# Arduboy_V2.net
KiCad netlist of a schematic drawn in Altium Designer
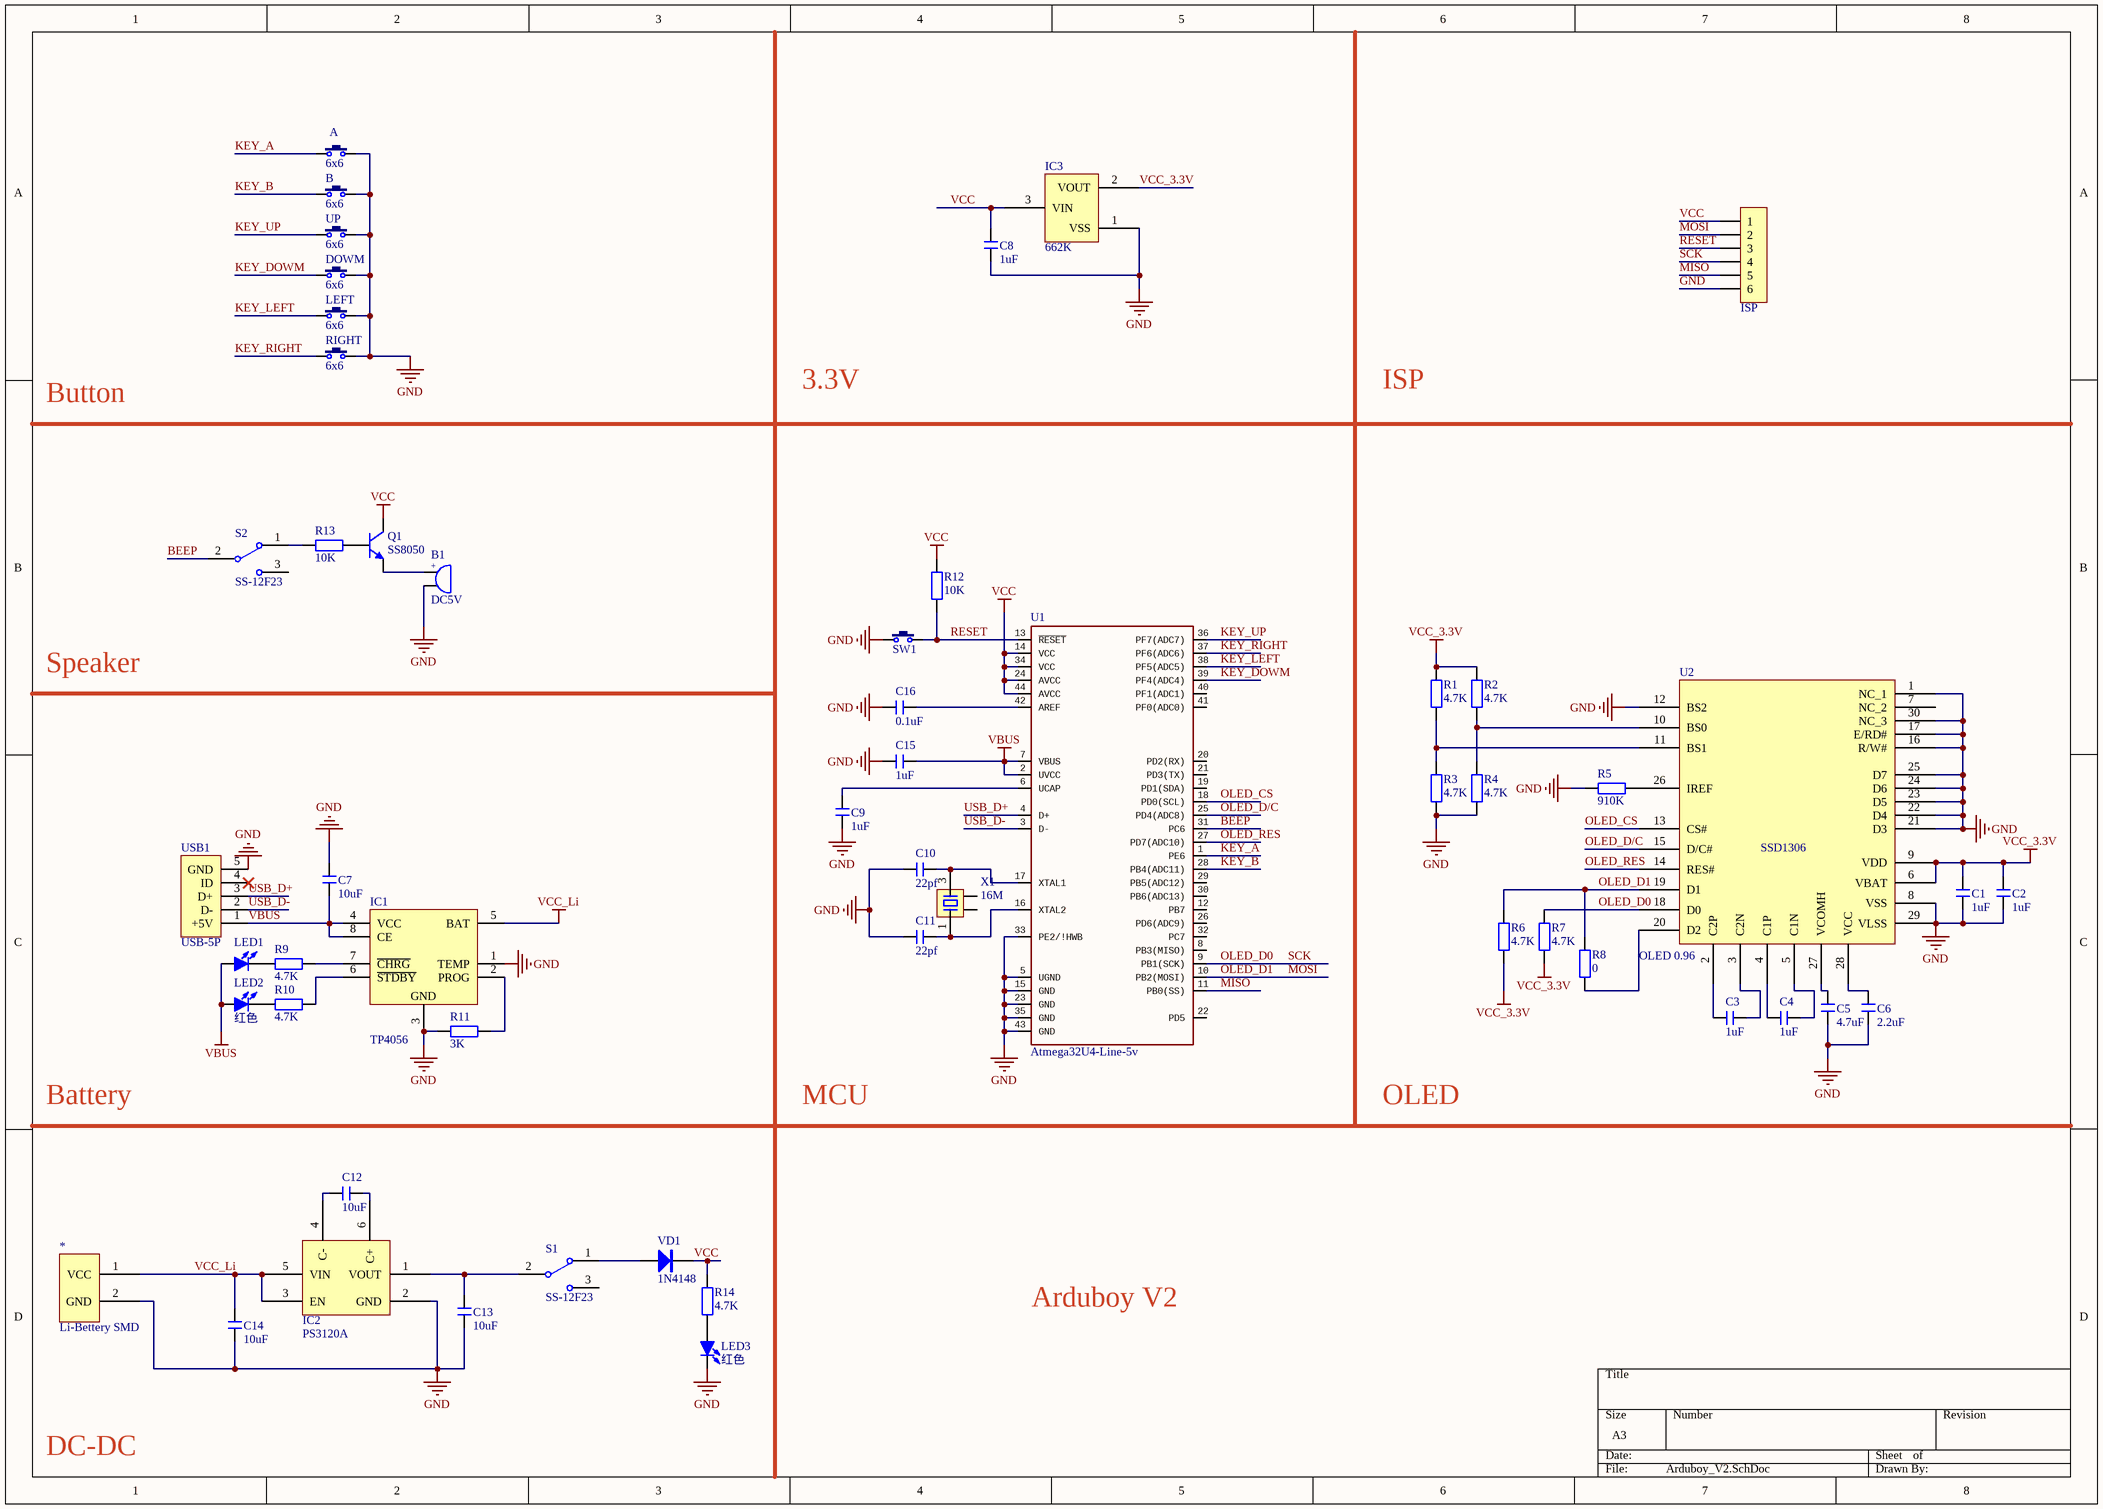
[diagram p0: Arduboy_V2.SchDoc]

(export (version "E")
  (design (tool "Eeschema 10.0.6"))
  (components
    (comp (ref "*")
      (value "Li-Bettery SMD")
      (footprint "Li-Bettery SMD")
      (libsource (lib "未分类器件") (part "Li-Bettery SMD"))
    )
    (comp (ref "A")
      (value "6x6")
      (footprint "SW SMD-2")
      (description "Arduboy 用")
      (libsource (lib "按键-开关") (part "SW SMD-2"))
    )
    (comp (ref "B")
      (value "6x6")
      (footprint "SW SMD-2")
      (description "Arduboy 用")
      (libsource (lib "按键-开关") (part "SW SMD-2"))
    )
    (comp (ref "B1")
      (value "DC5V")
      (footprint "BEEP-SMD 5x5x2")
      (description "蜂鸣器")
      (fields (field (name "版权归属") "黎明电子style"))
      (libsource (lib "未分类器件") (part "BEEP"))
    )
    (comp (ref "C1")
      (value "1uF")
      (footprint "C 0805")
      (description "无极性贴片电容")
      (fields (field (name "版权归属") "黎明电子style"))
      (libsource (lib "电阻-电容-电感") (part "C"))
    )
    (comp (ref "C2")
      (value "1uF")
      (footprint "C 0805")
      (description "无极性贴片电容")
      (fields (field (name "版权归属") "黎明电子style"))
      (libsource (lib "电阻-电容-电感") (part "C"))
    )
    (comp (ref "C3")
      (value "1uF")
      (footprint "C 0805")
      (description "无极性贴片电容")
      (fields (field (name "版权归属") "黎明电子style"))
      (libsource (lib "电阻-电容-电感") (part "C"))
    )
    (comp (ref "C4")
      (value "1uF")
      (footprint "C 0805")
      (description "无极性贴片电容")
      (fields (field (name "版权归属") "黎明电子style"))
      (libsource (lib "电阻-电容-电感") (part "C"))
    )
    (comp (ref "C5")
      (value "4.7uF")
      (footprint "C 0805")
      (description "无极性贴片电容")
      (fields (field (name "版权归属") "黎明电子style"))
      (libsource (lib "电阻-电容-电感") (part "C"))
    )
    (comp (ref "C6")
      (value "2.2uF")
      (footprint "C 0805")
      (description "无极性贴片电容")
      (fields (field (name "版权归属") "黎明电子style"))
      (libsource (lib "电阻-电容-电感") (part "C"))
    )
    (comp (ref "C7")
      (value "10uF")
      (footprint "C 0805")
      (description "无极性贴片电容")
      (fields (field (name "版权归属") "黎明电子style"))
      (libsource (lib "电阻-电容-电感") (part "C"))
    )
    (comp (ref "C8")
      (value "1uF")
      (footprint "C 0805")
      (description "无极性贴片电容")
      (fields (field (name "版权归属") "黎明电子style"))
      (libsource (lib "电阻-电容-电感") (part "C"))
    )
    (comp (ref "C9")
      (value "1uF")
      (footprint "C 0805")
      (description "无极性贴片电容")
      (fields (field (name "版权归属") "黎明电子style"))
      (libsource (lib "电阻-电容-电感") (part "C"))
    )
    (comp (ref "C10")
      (value "22pf")
      (footprint "C 0805")
      (description "无极性贴片电容")
      (fields (field (name "版权归属") "黎明电子style"))
      (libsource (lib "电阻-电容-电感") (part "C"))
    )
    (comp (ref "C11")
      (value "22pf")
      (footprint "C 0805")
      (description "无极性贴片电容")
      (fields (field (name "版权归属") "黎明电子style"))
      (libsource (lib "电阻-电容-电感") (part "C"))
    )
    (comp (ref "C12")
      (value "10uF")
      (footprint "C 0805")
      (description "无极性贴片电容")
      (fields (field (name "版权归属") "黎明电子style"))
      (libsource (lib "电阻-电容-电感") (part "C"))
    )
    (comp (ref "C13")
      (value "10uF")
      (footprint "C 0805")
      (description "无极性贴片电容")
      (fields (field (name "版权归属") "黎明电子style"))
      (libsource (lib "电阻-电容-电感") (part "C"))
    )
    (comp (ref "C14")
      (value "10uF")
      (footprint "C 0805")
      (description "无极性贴片电容")
      (fields (field (name "版权归属") "黎明电子style"))
      (libsource (lib "电阻-电容-电感") (part "C"))
    )
    (comp (ref "C15")
      (value "1uF")
      (footprint "C 0805")
      (description "无极性贴片电容")
      (fields (field (name "版权归属") "黎明电子style"))
      (libsource (lib "电阻-电容-电感") (part "C"))
    )
    (comp (ref "C16")
      (value "0.1uF")
      (footprint "C 0805")
      (description "无极性贴片电容")
      (fields (field (name "版权归属") "黎明电子style"))
      (libsource (lib "电阻-电容-电感") (part "C"))
    )
    (comp (ref "DOWM")
      (value "6x6")
      (footprint "SW SMD-2")
      (description "Arduboy 用")
      (libsource (lib "按键-开关") (part "SW SMD-2"))
    )
    (comp (ref "IC1")
      (value "TP4056")
      (footprint "SOP8_N")
      (description "锂电池充电管理")
      (fields (field (name "版权归属") "黎明电子style"))
      (libsource (lib "IC芯片") (part "TP4056"))
    )
    (comp (ref "IC2")
      (value "PS3120A")
      (footprint "SOT23-6M")
      (description "5V升压芯片")
      (libsource (lib "IC芯片") (part "PS3120A"))
    )
    (comp (ref "IC3")
      (value "662K")
      (footprint "SOT23-3M")
      (description "3.3V LEO稳压IC")
      (libsource (lib "IC芯片") (part "662K"))
    )
    (comp (ref "ISP")
      (value "HDR-1X6")
      (footprint "HDR-1X6")
      (description "6P接插件")
      (fields (field (name "版权归属") "黎明电子style"))
      (libsource (lib "接插件") (part "Header 6"))
    )
    (comp (ref "LED1")
      (value "~")
      (footprint "LED 0805B")
      (description "贴片LED")
      (fields (field (name "版权归属") "黎明电子style"))
      (libsource (lib "LED") (part "LED-SMD"))
    )
    (comp (ref "LED2")
      (value "红色")
      (footprint "LED 0805R")
      (description "贴片LED")
      (fields (field (name "版权归属") "黎明电子style"))
      (libsource (lib "LED") (part "LED-SMD"))
    )
    (comp (ref "LED3")
      (value "红色")
      (footprint "LED 0805B")
      (description "贴片LED")
      (fields (field (name "版权归属") "黎明电子style"))
      (libsource (lib "LED") (part "LED-SMD"))
    )
    (comp (ref "LEFT")
      (value "6x6")
      (footprint "SW SMD-2")
      (description "Arduboy 用")
      (libsource (lib "按键-开关") (part "SW SMD-2"))
    )
    (comp (ref "Q1")
      (value "SS8050")
      (footprint "SOT23-3M")
      (description "高频放大-NPN型")
      (fields (field (name "版权归属") "黎明电子style"))
      (libsource (lib "三极管") (part "8050-SMD"))
    )
    (comp (ref "R1")
      (value "4.7K")
      (footprint "R 0805")
      (description "贴片电阻")
      (fields (field (name "版权归属") "黎明电子style"))
      (libsource (lib "电阻-电容-电感") (part "R"))
    )
    (comp (ref "R2")
      (value "4.7K")
      (footprint "R 0805")
      (description "贴片电阻")
      (fields (field (name "版权归属") "黎明电子style"))
      (libsource (lib "电阻-电容-电感") (part "R"))
    )
    (comp (ref "R3")
      (value "4.7K")
      (footprint "R 0805")
      (description "贴片电阻")
      (fields (field (name "版权归属") "黎明电子style"))
      (libsource (lib "电阻-电容-电感") (part "R"))
    )
    (comp (ref "R4")
      (value "4.7K")
      (footprint "R 0805")
      (description "贴片电阻")
      (fields (field (name "版权归属") "黎明电子style"))
      (libsource (lib "电阻-电容-电感") (part "R"))
    )
    (comp (ref "R5")
      (value "910K")
      (footprint "R 0805")
      (description "贴片电阻")
      (fields (field (name "版权归属") "黎明电子style"))
      (libsource (lib "电阻-电容-电感") (part "R"))
    )
    (comp (ref "R6")
      (value "4.7K")
      (footprint "R 0805")
      (description "贴片电阻")
      (fields (field (name "版权归属") "黎明电子style"))
      (libsource (lib "电阻-电容-电感") (part "R"))
    )
    (comp (ref "R7")
      (value "4.7K")
      (footprint "R 0805")
      (description "贴片电阻")
      (fields (field (name "版权归属") "黎明电子style"))
      (libsource (lib "电阻-电容-电感") (part "R"))
    )
    (comp (ref "R8")
      (value "0")
      (footprint "R 0805")
      (description "贴片电阻")
      (fields (field (name "版权归属") "黎明电子style"))
      (libsource (lib "电阻-电容-电感") (part "R"))
    )
    (comp (ref "R9")
      (value "4.7K")
      (footprint "R 0805")
      (description "贴片电阻")
      (fields (field (name "版权归属") "黎明电子style"))
      (libsource (lib "电阻-电容-电感") (part "R"))
    )
    (comp (ref "R10")
      (value "4.7K")
      (footprint "R 0805")
      (description "贴片电阻")
      (fields (field (name "版权归属") "黎明电子style"))
      (libsource (lib "电阻-电容-电感") (part "R"))
    )
    (comp (ref "R11")
      (value "3K")
      (footprint "R 0805")
      (description "贴片电阻")
      (fields (field (name "版权归属") "黎明电子style"))
      (libsource (lib "电阻-电容-电感") (part "R"))
    )
    (comp (ref "R12")
      (value "10K")
      (footprint "R 0805")
      (description "贴片电阻")
      (fields (field (name "版权归属") "黎明电子style"))
      (libsource (lib "电阻-电容-电感") (part "R"))
    )
    (comp (ref "R13")
      (value "10K")
      (footprint "R 0805")
      (description "贴片电阻")
      (fields (field (name "版权归属") "黎明电子style"))
      (libsource (lib "电阻-电容-电感") (part "R"))
    )
    (comp (ref "R14")
      (value "4.7K")
      (footprint "R 0805")
      (description "贴片电阻")
      (fields (field (name "版权归属") "黎明电子style"))
      (libsource (lib "电阻-电容-电感") (part "R"))
    )
    (comp (ref "RIGHT")
      (value "6x6")
      (footprint "SW SMD-2")
      (description "Arduboy 用")
      (libsource (lib "按键-开关") (part "SW SMD-2"))
    )
    (comp (ref "S1")
      (value "SS-12F23")
      (footprint "MSK-12C01-07")
      (description "1路波动开关")
      (fields (field (name "版权归属") "黎明电子style"))
      (libsource (lib "按键-开关") (part "SSW-1P"))
    )
    (comp (ref "S2")
      (value "SS-12F23")
      (footprint "MSK-12C01-07")
      (description "1路波动开关")
      (fields (field (name "版权归属") "黎明电子style"))
      (libsource (lib "按键-开关") (part "SSW-1P"))
    )
    (comp (ref "SW1")
      (value "3x6x5")
      (footprint "TSW SMD-3*6*4.3")
      (description "3x6轻触开关")
      (fields (field (name "版权归属") "黎明电子style"))
      (libsource (lib "按键-开关") (part "TSW 3x6"))
    )
    (comp (ref "U1")
      (value "Atmega32U4-Line-5v")
      (footprint "TQFP44 10x10_M")
      (libsource (lib "Atmel系列单片机") (part "Atmega32U4-Line-5v"))
    )
    (comp (ref "U2") (value "OLED 0.96") (footprint "OLED 0.96") (libsource (lib "显示器件") (part "OLED 0.96")))
    (comp (ref "UP")
      (value "6x6")
      (footprint "SW SMD-2")
      (description "Arduboy 用")
      (libsource (lib "按键-开关") (part "SW SMD-2"))
    )
    (comp (ref "USB1")
      (value "USB-5P")
      (footprint "USB-MICRO_B")
      (description "微型USB母座")
      (fields (field (name "版权归属") "黎明电子style"))
      (libsource (lib "接口类") (part "USB-5P"))
    )
    (comp (ref "VD1")
      (value "1N4148")
      (footprint "SOD-323")
      (description "高速开关二极管")
      (fields (field (name "版权归属") "黎明电子style"))
      (libsource (lib "二极管-整流桥") (part "1N4148"))
    )
    (comp (ref "X1")
      (value "16M")
      (footprint "XTAL-5032")
      (description "4脚晶振")
      (fields (field (name "版权归属") "黎明电子style"))
      (libsource (lib "保险丝-晶振") (part "XTAL-4"))
    )
  )
  (nets
    (net (code "1") (name "/BEEP") (class "Default")
      (node (ref "S2") (pin "2") (pinfunction "2_2") (pintype "passive"))
      (node (ref "U1") (pin "31") (pinfunction "PC6_31") (pintype "passive"))
    )
    (net (code "2") (name "/KEY_A") (class "Default")
      (node (ref "A") (pin "1") (pinfunction "1_1") (pintype "passive"))
      (node (ref "U1") (pin "1") (pinfunction "PE6_1") (pintype "passive"))
    )
    (net (code "3") (name "/KEY_B") (class "Default")
      (node (ref "B") (pin "1") (pinfunction "1_1") (pintype "passive"))
      (node (ref "U1") (pin "28") (pinfunction "PB4(ADC11)_28") (pintype "passive"))
    )
    (net (code "4") (name "/KEY_DOWM") (class "Default")
      (node (ref "DOWM") (pin "1") (pinfunction "1_1") (pintype "passive"))
      (node (ref "U1") (pin "39") (pinfunction "PF4(ADC4)_39") (pintype "passive"))
    )
    (net (code "5") (name "/KEY_LEFT") (class "Default")
      (node (ref "LEFT") (pin "1") (pinfunction "1_1") (pintype "passive"))
      (node (ref "U1") (pin "38") (pinfunction "PF5(ADC5)_38") (pintype "passive"))
    )
    (net (code "6") (name "/KEY_RIGHT") (class "Default")
      (node (ref "RIGHT") (pin "1") (pinfunction "1_1") (pintype "passive"))
      (node (ref "U1") (pin "37") (pinfunction "PF6(ADC6)_37") (pintype "passive"))
    )
    (net (code "7") (name "/KEY_UP") (class "Default")
      (node (ref "U1") (pin "36") (pinfunction "PF7(ADC7)_36") (pintype "passive"))
      (node (ref "UP") (pin "1") (pinfunction "1_1") (pintype "passive"))
    )
    (net (code "8") (name "/MISO") (class "Default")
      (node (ref "ISP") (pin "5") (pinfunction "5_5") (pintype "passive"))
      (node (ref "U1") (pin "11") (pinfunction "PB0(SS)_11") (pintype "passive"))
    )
    (net (code "9") (name "/MOSI") (class "Default")
      (node (ref "ISP") (pin "2") (pinfunction "2_2") (pintype "passive"))
      (node (ref "R6") (pin "2") (pinfunction "2_2") (pintype "passive"))
      (node (ref "R8") (pin "2") (pinfunction "2_2") (pintype "passive"))
      (node (ref "U1") (pin "10") (pinfunction "PB2(MOSI)_10") (pintype "passive"))
      (node (ref "U2") (pin "19") (pinfunction "D1_19") (pintype "passive"))
    )
    (net (code "10") (name "/OLED_CS") (class "Default")
      (node (ref "U1") (pin "18") (pinfunction "PD0(SCL)_18") (pintype "passive"))
      (node (ref "U2") (pin "13") (pinfunction "CS#_13") (pintype "passive"))
    )
    (net (code "11") (name "/OLED_D0") (class "Default")
      (node (ref "ISP") (pin "4") (pinfunction "4_4") (pintype "passive"))
      (node (ref "R7") (pin "2") (pinfunction "2_2") (pintype "passive"))
      (node (ref "U1") (pin "9") (pinfunction "PB1(SCK)_9") (pintype "passive"))
      (node (ref "U2") (pin "18") (pinfunction "D0_18") (pintype "passive"))
    )
    (net (code "12") (name "/OLED_D{slash}C") (class "Default")
      (node (ref "U1") (pin "25") (pinfunction "PD4(ADC8)_25") (pintype "passive"))
      (node (ref "U2") (pin "15") (pinfunction "D/C#_15") (pintype "passive"))
    )
    (net (code "13") (name "/OLED_RES") (class "Default")
      (node (ref "U1") (pin "27") (pinfunction "PD7(ADC10)_27") (pintype "passive"))
      (node (ref "U2") (pin "14") (pinfunction "RES#_14") (pintype "passive"))
    )
    (net (code "14") (name "/RESET") (class "Default")
      (node (ref "ISP") (pin "3") (pinfunction "3_3") (pintype "passive"))
      (node (ref "R12") (pin "1") (pinfunction "1_1") (pintype "passive"))
      (node (ref "SW1") (pin "2") (pinfunction "2_2") (pintype "passive"))
      (node (ref "U1") (pin "13") (pinfunction "~{RESET}_13") (pintype "passive"))
    )
    (net (code "15") (name "/USB_D+") (class "Default")
      (node (ref "U1") (pin "4") (pinfunction "D+_4") (pintype "passive"))
      (node (ref "USB1") (pin "3") (pinfunction "D+_3") (pintype "passive"))
    )
    (net (code "16") (name "/USB_D-") (class "Default")
      (node (ref "U1") (pin "3") (pinfunction "D-_3") (pintype "passive"))
      (node (ref "USB1") (pin "2") (pinfunction "D-_2") (pintype "passive"))
    )
    (net (code "17") (name "GND") (class "Default")
      (node (ref "*") (pin "2") (pinfunction "GND_2") (pintype "passive"))
      (node (ref "A") (pin "2") (pinfunction "2_2") (pintype "passive"))
      (node (ref "B") (pin "2") (pinfunction "2_2") (pintype "passive"))
      (node (ref "B1") (pin "2") (pinfunction "2_2") (pintype "passive"))
      (node (ref "C1") (pin "1") (pinfunction "1_1") (pintype "passive"))
      (node (ref "C10") (pin "1") (pinfunction "1_1") (pintype "passive"))
      (node (ref "C11") (pin "1") (pinfunction "1_1") (pintype "passive"))
      (node (ref "C13") (pin "1") (pinfunction "1_1") (pintype "passive"))
      (node (ref "C14") (pin "1") (pinfunction "1_1") (pintype "passive"))
      (node (ref "C15") (pin "1") (pinfunction "1_1") (pintype "passive"))
      (node (ref "C16") (pin "1") (pinfunction "1_1") (pintype "passive"))
      (node (ref "C2") (pin "1") (pinfunction "1_1") (pintype "passive"))
      (node (ref "C5") (pin "1") (pinfunction "1_1") (pintype "passive"))
      (node (ref "C6") (pin "1") (pinfunction "1_1") (pintype "passive"))
      (node (ref "C7") (pin "2") (pinfunction "2_2") (pintype "passive"))
      (node (ref "C8") (pin "2") (pinfunction "2_2") (pintype "passive"))
      (node (ref "C9") (pin "2") (pinfunction "2_2") (pintype "passive"))
      (node (ref "DOWM") (pin "2") (pinfunction "2_2") (pintype "passive"))
      (node (ref "IC1") (pin "1") (pinfunction "TEMP_1") (pintype "passive"))
      (node (ref "IC1") (pin "3") (pinfunction "GND_3") (pintype "passive"))
      (node (ref "IC2") (pin "2") (pinfunction "GND_2") (pintype "passive"))
      (node (ref "IC3") (pin "1") (pinfunction "VSS_1") (pintype "passive"))
      (node (ref "ISP") (pin "6") (pinfunction "6_6") (pintype "passive"))
      (node (ref "LED3") (pin "2") (pinfunction "K_2") (pintype "passive"))
      (node (ref "LEFT") (pin "2") (pinfunction "2_2") (pintype "passive"))
      (node (ref "R11") (pin "1") (pinfunction "1_1") (pintype "passive"))
      (node (ref "R3") (pin "1") (pinfunction "1_1") (pintype "passive"))
      (node (ref "R4") (pin "1") (pinfunction "1_1") (pintype "passive"))
      (node (ref "R5") (pin "1") (pinfunction "1_1") (pintype "passive"))
      (node (ref "RIGHT") (pin "2") (pinfunction "2_2") (pintype "passive"))
      (node (ref "SW1") (pin "1") (pinfunction "1_1") (pintype "passive"))
      (node (ref "U1") (pin "15") (pinfunction "GND_15") (pintype "passive"))
      (node (ref "U1") (pin "23") (pinfunction "GND_23") (pintype "passive"))
      (node (ref "U1") (pin "33") (pinfunction "PE2/!HWB_33") (pintype "passive"))
      (node (ref "U1") (pin "35") (pinfunction "GND_35") (pintype "passive"))
      (node (ref "U1") (pin "43") (pinfunction "GND_43") (pintype "passive"))
      (node (ref "U1") (pin "5") (pinfunction "UGND_5") (pintype "passive"))
      (node (ref "U2") (pin "1") (pinfunction "NC_1_1") (pintype "passive"))
      (node (ref "U2") (pin "12") (pinfunction "BS2_12") (pintype "passive"))
      (node (ref "U2") (pin "16") (pinfunction "R/W#_16") (pintype "passive"))
      (node (ref "U2") (pin "17") (pinfunction "E/RD#_17") (pintype "passive"))
      (node (ref "U2") (pin "21") (pinfunction "D3_21") (pintype "passive"))
      (node (ref "U2") (pin "22") (pinfunction "D4_22") (pintype "passive"))
      (node (ref "U2") (pin "23") (pinfunction "D5_23") (pintype "passive"))
      (node (ref "U2") (pin "24") (pinfunction "D6_24") (pintype "passive"))
      (node (ref "U2") (pin "25") (pinfunction "D7_25") (pintype "passive"))
      (node (ref "U2") (pin "29") (pinfunction "VLSS_29") (pintype "passive"))
      (node (ref "U2") (pin "30") (pinfunction "NC_3_30") (pintype "passive"))
      (node (ref "U2") (pin "8") (pinfunction "VSS_8") (pintype "passive"))
      (node (ref "UP") (pin "2") (pinfunction "2_2") (pintype "passive"))
      (node (ref "USB1") (pin "5") (pinfunction "GND_5") (pintype "passive"))
    )
    (net (code "18") (name "Net-(IC1-PROG)") (class "Default")
      (node (ref "IC1") (pin "2") (pinfunction "PROG_2") (pintype "passive"))
      (node (ref "R11") (pin "2") (pinfunction "2_2") (pintype "passive"))
    )
    (net (code "19") (name "Net-(IC1-~{CHRG})") (class "Default")
      (node (ref "IC1") (pin "7") (pinfunction "~{CHRG}_7") (pintype "passive"))
      (node (ref "R9") (pin "2") (pinfunction "2_2") (pintype "passive"))
    )
    (net (code "20") (name "Net-(IC1-~{STDBY})") (class "Default")
      (node (ref "IC1") (pin "6") (pinfunction "~{STDBY}_6") (pintype "passive"))
      (node (ref "R10") (pin "2") (pinfunction "2_2") (pintype "passive"))
    )
    (net (code "21") (name "Net-(IC2-C+)") (class "Default")
      (node (ref "C12") (pin "2") (pinfunction "2_2") (pintype "passive"))
      (node (ref "IC2") (pin "6") (pinfunction "C+_6") (pintype "passive"))
    )
    (net (code "22") (name "Net-(IC2-C-)") (class "Default")
      (node (ref "C12") (pin "1") (pinfunction "1_1") (pintype "passive"))
      (node (ref "IC2") (pin "4") (pinfunction "C-_4") (pintype "passive"))
    )
    (net (code "23") (name "Net-(IC2-VOUT)") (class "Default")
      (node (ref "C13") (pin "2") (pinfunction "2_2") (pintype "passive"))
      (node (ref "IC2") (pin "1") (pinfunction "VOUT_1") (pintype "passive"))
      (node (ref "S1") (pin "2") (pinfunction "2_2") (pintype "passive"))
    )
    (net (code "24") (name "Net-(LED1-K)") (class "Default")
      (node (ref "LED1") (pin "2") (pinfunction "K_2") (pintype "passive"))
      (node (ref "R9") (pin "1") (pinfunction "1_1") (pintype "passive"))
    )
    (net (code "25") (name "Net-(LED2-K)") (class "Default")
      (node (ref "LED2") (pin "2") (pinfunction "K_2") (pintype "passive"))
      (node (ref "R10") (pin "1") (pinfunction "1_1") (pintype "passive"))
    )
    (net (code "26") (name "Net-(LED3-A)") (class "Default")
      (node (ref "LED3") (pin "1") (pinfunction "A_1") (pintype "passive"))
      (node (ref "R14") (pin "1") (pinfunction "1_1") (pintype "passive"))
    )
    (net (code "27") (name "Net-(Q1-B)") (class "Default")
      (node (ref "Q1") (pin "1") (pinfunction "B_1") (pintype "passive"))
      (node (ref "R13") (pin "2") (pinfunction "2_2") (pintype "passive"))
    )
    (net (code "28") (name "Net-(Q1-E)") (class "Default")
      (node (ref "B1") (pin "1") (pinfunction "1_1") (pintype "passive"))
      (node (ref "Q1") (pin "2") (pinfunction "E_2") (pintype "passive"))
    )
    (net (code "29") (name "Net-(R13-Pad1)") (class "Default")
      (node (ref "R13") (pin "1") (pinfunction "1_1") (pintype "passive"))
      (node (ref "S2") (pin "1") (pinfunction "1_1") (pintype "passive"))
    )
    (net (code "30") (name "Net-(U1-AREF)") (class "Default")
      (node (ref "C16") (pin "2") (pinfunction "2_2") (pintype "passive"))
      (node (ref "U1") (pin "42") (pinfunction "AREF_42") (pintype "passive"))
    )
    (net (code "31") (name "Net-(U1-UCAP)") (class "Default")
      (node (ref "C9") (pin "1") (pinfunction "1_1") (pintype "passive"))
      (node (ref "U1") (pin "6") (pinfunction "UCAP_6") (pintype "passive"))
    )
    (net (code "32") (name "Net-(U1-XTAL1)") (class "Default")
      (node (ref "C10") (pin "2") (pinfunction "2_2") (pintype "passive"))
      (node (ref "U1") (pin "17") (pinfunction "XTAL1_17") (pintype "passive"))
      (node (ref "X1") (pin "3") (pinfunction "3_3") (pintype "passive"))
    )
    (net (code "33") (name "Net-(U1-XTAL2)") (class "Default")
      (node (ref "C11") (pin "2") (pinfunction "2_2") (pintype "passive"))
      (node (ref "U1") (pin "16") (pinfunction "XTAL2_16") (pintype "passive"))
      (node (ref "X1") (pin "1") (pinfunction "1_1") (pintype "passive"))
    )
    (net (code "34") (name "Net-(U2-BS0)") (class "Default")
      (node (ref "R2") (pin "1") (pinfunction "1_1") (pintype "passive"))
      (node (ref "R4") (pin "2") (pinfunction "2_2") (pintype "passive"))
      (node (ref "U2") (pin "10") (pinfunction "BS0_10") (pintype "passive"))
    )
    (net (code "35") (name "Net-(U2-BS1)") (class "Default")
      (node (ref "R1") (pin "1") (pinfunction "1_1") (pintype "passive"))
      (node (ref "R3") (pin "2") (pinfunction "2_2") (pintype "passive"))
      (node (ref "U2") (pin "11") (pinfunction "BS1_11") (pintype "passive"))
    )
    (net (code "36") (name "Net-(U2-C1N)") (class "Default")
      (node (ref "C4") (pin "2") (pinfunction "2_2") (pintype "passive"))
      (node (ref "U2") (pin "5") (pinfunction "C1N_5") (pintype "passive"))
    )
    (net (code "37") (name "Net-(U2-C1P)") (class "Default")
      (node (ref "C4") (pin "1") (pinfunction "1_1") (pintype "passive"))
      (node (ref "U2") (pin "4") (pinfunction "C1P_4") (pintype "passive"))
    )
    (net (code "38") (name "Net-(U2-C2N)") (class "Default")
      (node (ref "C3") (pin "2") (pinfunction "2_2") (pintype "passive"))
      (node (ref "U2") (pin "3") (pinfunction "C2N_3") (pintype "passive"))
    )
    (net (code "39") (name "Net-(U2-C2P)") (class "Default")
      (node (ref "C3") (pin "1") (pinfunction "1_1") (pintype "passive"))
      (node (ref "U2") (pin "2") (pinfunction "C2P_2") (pintype "passive"))
    )
    (net (code "40") (name "Net-(U2-D2)") (class "Default")
      (node (ref "R8") (pin "1") (pinfunction "1_1") (pintype "passive"))
      (node (ref "U2") (pin "20") (pinfunction "D2_20") (pintype "passive"))
    )
    (net (code "41") (name "Net-(U2-IREF)") (class "Default")
      (node (ref "R5") (pin "2") (pinfunction "2_2") (pintype "passive"))
      (node (ref "U2") (pin "26") (pinfunction "IREF_26") (pintype "passive"))
    )
    (net (code "42") (name "Net-(U2-VCC)") (class "Default")
      (node (ref "C6") (pin "2") (pinfunction "2_2") (pintype "passive"))
      (node (ref "U2") (pin "28") (pinfunction "VCC_28") (pintype "passive"))
    )
    (net (code "43") (name "Net-(U2-VCOMH)") (class "Default")
      (node (ref "C5") (pin "2") (pinfunction "2_2") (pintype "passive"))
      (node (ref "U2") (pin "27") (pinfunction "VCOMH_27") (pintype "passive"))
    )
    (net (code "44") (name "Net-(VD1-A)") (class "Default")
      (node (ref "S1") (pin "1") (pinfunction "1_1") (pintype "passive"))
      (node (ref "VD1") (pin "1") (pinfunction "A_1") (pintype "passive"))
    )
    (net (code "45") (name "VBUS") (class "Default")
      (node (ref "C15") (pin "2") (pinfunction "2_2") (pintype "passive"))
      (node (ref "C7") (pin "1") (pinfunction "1_1") (pintype "passive"))
      (node (ref "IC1") (pin "4") (pinfunction "VCC_4") (pintype "passive"))
      (node (ref "IC1") (pin "8") (pinfunction "CE_8") (pintype "passive"))
      (node (ref "LED1") (pin "1") (pinfunction "A_1") (pintype "passive"))
      (node (ref "LED2") (pin "1") (pinfunction "A_1") (pintype "passive"))
      (node (ref "U1") (pin "2") (pinfunction "UVCC_2") (pintype "passive"))
      (node (ref "U1") (pin "7") (pinfunction "VBUS_7") (pintype "passive"))
      (node (ref "USB1") (pin "1") (pinfunction "+5V_1") (pintype "passive"))
    )
    (net (code "46") (name "VCC") (class "Default")
      (node (ref "C8") (pin "1") (pinfunction "1_1") (pintype "passive"))
      (node (ref "IC3") (pin "3") (pinfunction "VIN_3") (pintype "passive"))
      (node (ref "ISP") (pin "1") (pinfunction "1_1") (pintype "passive"))
      (node (ref "Q1") (pin "3") (pinfunction "C_3") (pintype "passive"))
      (node (ref "R12") (pin "2") (pinfunction "2_2") (pintype "passive"))
      (node (ref "R14") (pin "2") (pinfunction "2_2") (pintype "passive"))
      (node (ref "U1") (pin "14") (pinfunction "VCC_14") (pintype "passive"))
      (node (ref "U1") (pin "24") (pinfunction "AVCC_24") (pintype "passive"))
      (node (ref "U1") (pin "34") (pinfunction "VCC_34") (pintype "passive"))
      (node (ref "U1") (pin "44") (pinfunction "AVCC_44") (pintype "passive"))
      (node (ref "VD1") (pin "2") (pinfunction "K_2") (pintype "passive"))
    )
    (net (code "47") (name "VCC_3.3V") (class "Default")
      (node (ref "C1") (pin "2") (pinfunction "2_2") (pintype "passive"))
      (node (ref "C2") (pin "2") (pinfunction "2_2") (pintype "passive"))
      (node (ref "IC3") (pin "2") (pinfunction "VOUT_2") (pintype "passive"))
      (node (ref "R1") (pin "2") (pinfunction "2_2") (pintype "passive"))
      (node (ref "R2") (pin "2") (pinfunction "2_2") (pintype "passive"))
      (node (ref "R6") (pin "1") (pinfunction "1_1") (pintype "passive"))
      (node (ref "R7") (pin "1") (pinfunction "1_1") (pintype "passive"))
      (node (ref "U2") (pin "6") (pinfunction "VBAT_6") (pintype "passive"))
      (node (ref "U2") (pin "9") (pinfunction "VDD_9") (pintype "passive"))
    )
    (net (code "48") (name "VCC_Li") (class "Default")
      (node (ref "*") (pin "1") (pinfunction "VCC_1") (pintype "passive"))
      (node (ref "C14") (pin "2") (pinfunction "2_2") (pintype "passive"))
      (node (ref "IC1") (pin "5") (pinfunction "BAT_5") (pintype "passive"))
      (node (ref "IC2") (pin "3") (pinfunction "EN_3") (pintype "passive"))
      (node (ref "IC2") (pin "5") (pinfunction "VIN_5") (pintype "passive"))
    )
    (net (code "49") (name "unconnected-(S1-Pad3)") (class "Default")
      (node (ref "S1") (pin "3") (pinfunction "3_3") (pintype "passive"))
    )
    (net (code "50") (name "unconnected-(S2-Pad3)") (class "Default")
      (node (ref "S2") (pin "3") (pinfunction "3_3") (pintype "passive"))
    )
    (net (code "51") (name "unconnected-(U1-PB3(MISO)-Pad8)") (class "Default")
      (node (ref "U1") (pin "8") (pinfunction "PB3(MISO)_8") (pintype "passive"))
    )
    (net (code "52") (name "unconnected-(U1-PB5(ADC12)-Pad29)") (class "Default")
      (node (ref "U1") (pin "29") (pinfunction "PB5(ADC12)_29") (pintype "passive"))
    )
    (net (code "53") (name "unconnected-(U1-PB6(ADC13)-Pad30)") (class "Default")
      (node (ref "U1") (pin "30") (pinfunction "PB6(ADC13)_30") (pintype "passive"))
    )
    (net (code "54") (name "unconnected-(U1-PB7-Pad12)") (class "Default")
      (node (ref "U1") (pin "12") (pinfunction "PB7_12") (pintype "passive"))
    )
    (net (code "55") (name "unconnected-(U1-PC7-Pad32)") (class "Default")
      (node (ref "U1") (pin "32") (pinfunction "PC7_32") (pintype "passive"))
    )
    (net (code "56") (name "unconnected-(U1-PD1(SDA)-Pad19)") (class "Default")
      (node (ref "U1") (pin "19") (pinfunction "PD1(SDA)_19") (pintype "passive"))
    )
    (net (code "57") (name "unconnected-(U1-PD2(RX)-Pad20)") (class "Default")
      (node (ref "U1") (pin "20") (pinfunction "PD2(RX)_20") (pintype "passive"))
    )
    (net (code "58") (name "unconnected-(U1-PD3(TX)-Pad21)") (class "Default")
      (node (ref "U1") (pin "21") (pinfunction "PD3(TX)_21") (pintype "passive"))
    )
    (net (code "59") (name "unconnected-(U1-PD5-Pad22)") (class "Default")
      (node (ref "U1") (pin "22") (pinfunction "PD5_22") (pintype "passive"))
    )
    (net (code "60") (name "unconnected-(U1-PD6(ADC9)-Pad26)") (class "Default")
      (node (ref "U1") (pin "26") (pinfunction "PD6(ADC9)_26") (pintype "passive"))
    )
    (net (code "61") (name "unconnected-(U1-PF0(ADC0)-Pad41)") (class "Default")
      (node (ref "U1") (pin "41") (pinfunction "PF0(ADC0)_41") (pintype "passive"))
    )
    (net (code "62") (name "unconnected-(U1-PF1(ADC1)-Pad40)") (class "Default")
      (node (ref "U1") (pin "40") (pinfunction "PF1(ADC1)_40") (pintype "passive"))
    )
    (net (code "63") (name "unconnected-(U2-NC_2-Pad7)") (class "Default")
      (node (ref "U2") (pin "7") (pinfunction "NC_2_7") (pintype "passive"))
    )
    (net (code "64") (name "unconnected-(USB1-ID-Pad4)") (class "Default")
      (node (ref "USB1") (pin "4") (pinfunction "ID_4") (pintype "passive+no_connect"))
    )
    (net (code "65") (name "unconnected-(X1-Pad2)") (class "Default")
      (node (ref "X1") (pin "2") (pinfunction "2_2") (pintype "passive"))
    )
    (net (code "66") (name "unconnected-(X1-Pad4)") (class "Default")
      (node (ref "X1") (pin "4") (pinfunction "4_4") (pintype "passive"))
    )
  )
)
